# main.net
KiCad netlist of a schematic drawn in EAGLE
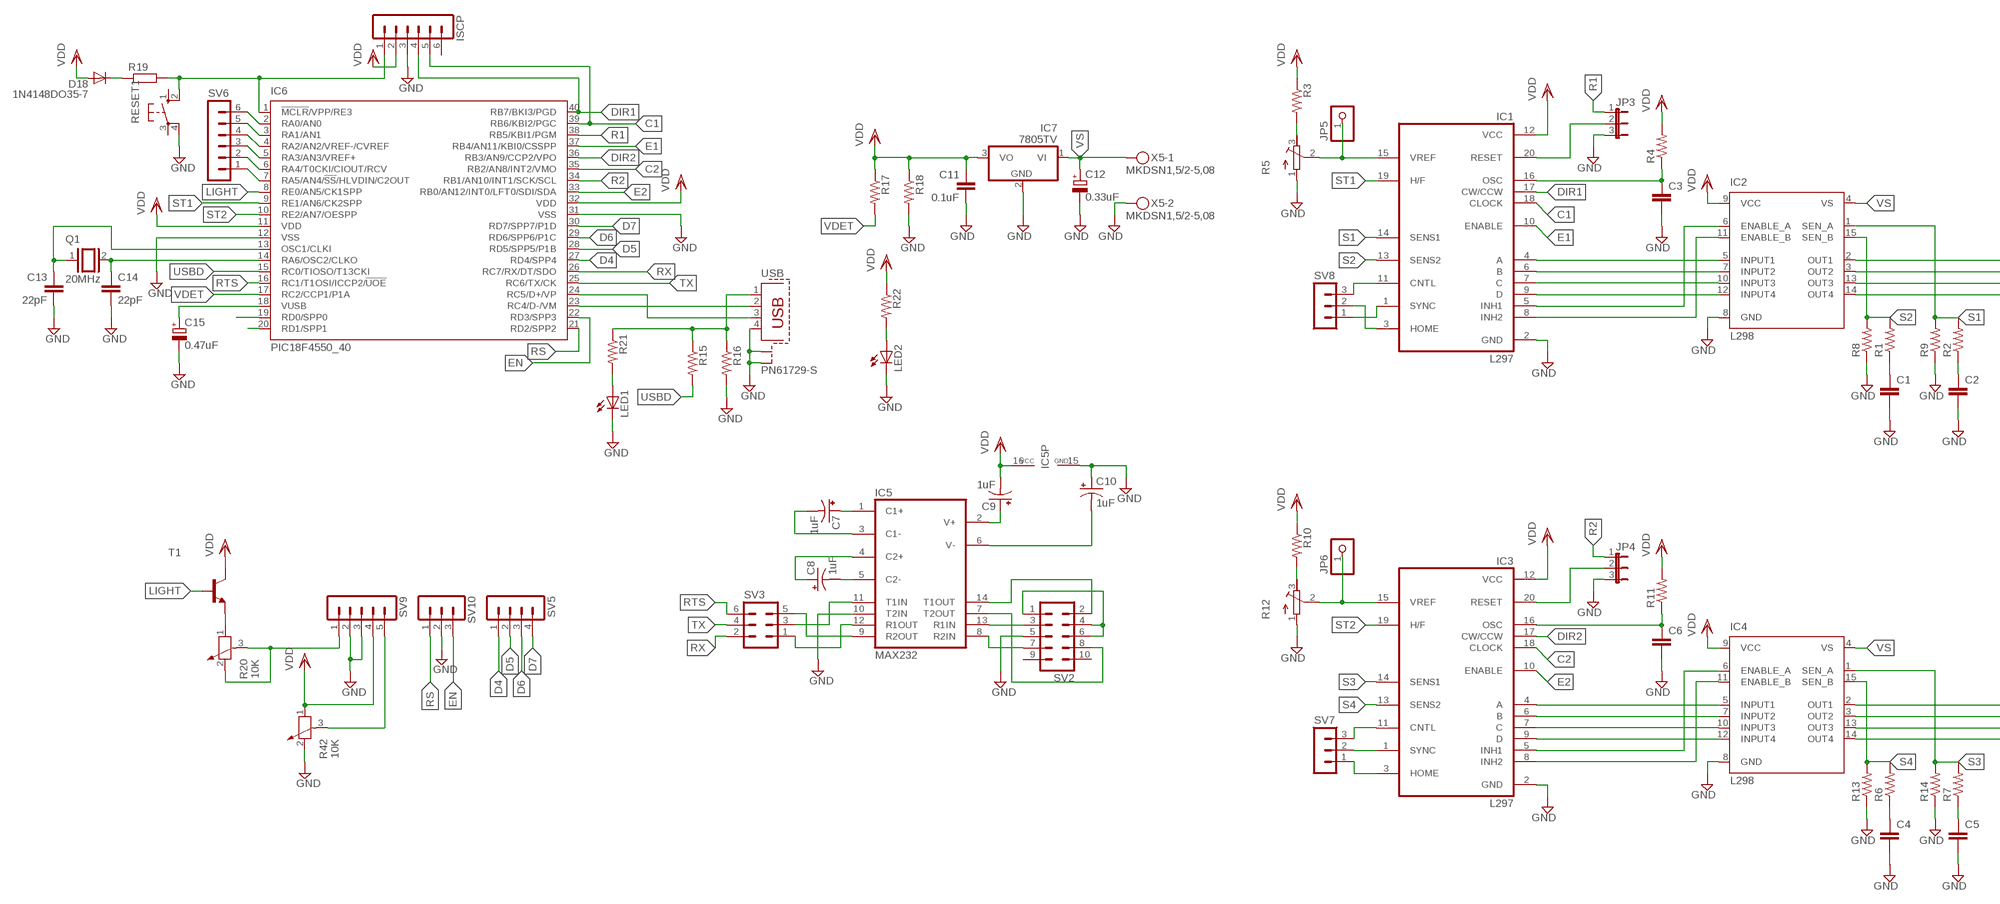
[diagram p0: schematic, sheet 1, part 1 of 2]
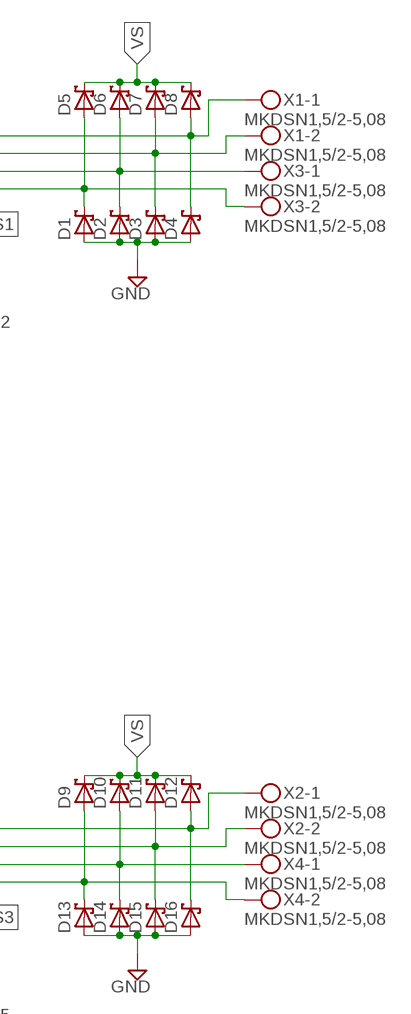
[diagram p1: schematic, sheet 1, part 2 of 2]

(export (version "E")
  (design (tool "Eeschema 10.0.6"))
  (components
    (comp (ref "C1")
      (value "C2.5/2")
      (footprint "eagle-import:C2.5-2")
      (libsource (lib "eagle-import") (part "C2.5/2"))
    )
    (comp (ref "C2")
      (value "C2.5/2")
      (footprint "eagle-import:C2.5-2")
      (libsource (lib "eagle-import") (part "C2.5/2"))
    )
    (comp (ref "C3")
      (value "C2.5/2")
      (footprint "eagle-import:C2.5-2")
      (libsource (lib "eagle-import") (part "C2.5/2"))
    )
    (comp (ref "C4")
      (value "C2.5/2")
      (footprint "eagle-import:C2.5-2")
      (libsource (lib "eagle-import") (part "C2.5/2"))
    )
    (comp (ref "C5")
      (value "C2.5/2")
      (footprint "eagle-import:C2.5-2")
      (libsource (lib "eagle-import") (part "C2.5/2"))
    )
    (comp (ref "C6")
      (value "C2.5/2")
      (footprint "eagle-import:C2.5-2")
      (libsource (lib "eagle-import") (part "C2.5/2"))
    )
    (comp (ref "C7")
      (value "1uF")
      (footprint "eagle-import:E2,5-6")
      (libsource (lib "eagle-import") (part "CPOL-USE2.5-6"))
    )
    (comp (ref "C8")
      (value "1uF")
      (footprint "eagle-import:E2,5-6")
      (libsource (lib "eagle-import") (part "CPOL-USE2.5-6"))
    )
    (comp (ref "C9")
      (value "1uF")
      (footprint "eagle-import:E2,5-6")
      (libsource (lib "eagle-import") (part "CPOL-USE2.5-6"))
    )
    (comp (ref "C10")
      (value "1uF")
      (footprint "eagle-import:E2,5-6")
      (libsource (lib "eagle-import") (part "CPOL-USE2.5-6"))
    )
    (comp (ref "C11")
      (value "0.1uF")
      (footprint "eagle-import:C025-025X050")
      (libsource (lib "eagle-import") (part "C-EU025-025X050"))
    )
    (comp (ref "C12")
      (value "0.33uF")
      (footprint "eagle-import:E2,5-6")
      (libsource (lib "eagle-import") (part "CPOL-EUE2.5-6"))
    )
    (comp (ref "C13")
      (value "22pF")
      (footprint "eagle-import:C025-024X044")
      (libsource (lib "eagle-import") (part "C-EU025-024X044"))
    )
    (comp (ref "C14")
      (value "22pF")
      (footprint "eagle-import:C025-024X044")
      (libsource (lib "eagle-import") (part "C-EU025-024X044"))
    )
    (comp (ref "C15")
      (value "0.47uF")
      (footprint "eagle-import:E2,5-6")
      (libsource (lib "eagle-import") (part "CPOL-EUE2.5-6"))
    )
    (comp (ref "D1")
      (value "SCHOTTKY-DIODEDO201T15")
      (footprint "eagle-import:DO201T15")
      (libsource (lib "eagle-import") (part "SCHOTTKY-DIODEDO201T15"))
    )
    (comp (ref "D2")
      (value "SCHOTTKY-DIODEDO201T15")
      (footprint "eagle-import:DO201T15")
      (libsource (lib "eagle-import") (part "SCHOTTKY-DIODEDO201T15"))
    )
    (comp (ref "D3")
      (value "SCHOTTKY-DIODEDO201T15")
      (footprint "eagle-import:DO201T15")
      (libsource (lib "eagle-import") (part "SCHOTTKY-DIODEDO201T15"))
    )
    (comp (ref "D4")
      (value "SCHOTTKY-DIODEDO201T15")
      (footprint "eagle-import:DO201T15")
      (libsource (lib "eagle-import") (part "SCHOTTKY-DIODEDO201T15"))
    )
    (comp (ref "D5")
      (value "SCHOTTKY-DIODEDO201T15")
      (footprint "eagle-import:DO201T15")
      (libsource (lib "eagle-import") (part "SCHOTTKY-DIODEDO201T15"))
    )
    (comp (ref "D6")
      (value "SCHOTTKY-DIODEDO201T15")
      (footprint "eagle-import:DO201T15")
      (libsource (lib "eagle-import") (part "SCHOTTKY-DIODEDO201T15"))
    )
    (comp (ref "D7")
      (value "SCHOTTKY-DIODEDO201T15")
      (footprint "eagle-import:DO201T15")
      (libsource (lib "eagle-import") (part "SCHOTTKY-DIODEDO201T15"))
    )
    (comp (ref "D8")
      (value "SCHOTTKY-DIODEDO201T15")
      (footprint "eagle-import:DO201T15")
      (libsource (lib "eagle-import") (part "SCHOTTKY-DIODEDO201T15"))
    )
    (comp (ref "D9")
      (value "SCHOTTKY-DIODEDO201T15")
      (footprint "eagle-import:DO201T15")
      (libsource (lib "eagle-import") (part "SCHOTTKY-DIODEDO201T15"))
    )
    (comp (ref "D10")
      (value "SCHOTTKY-DIODEDO201T15")
      (footprint "eagle-import:DO201T15")
      (libsource (lib "eagle-import") (part "SCHOTTKY-DIODEDO201T15"))
    )
    (comp (ref "D11")
      (value "SCHOTTKY-DIODEDO201T15")
      (footprint "eagle-import:DO201T15")
      (libsource (lib "eagle-import") (part "SCHOTTKY-DIODEDO201T15"))
    )
    (comp (ref "D12")
      (value "SCHOTTKY-DIODEDO201T15")
      (footprint "eagle-import:DO201T15")
      (libsource (lib "eagle-import") (part "SCHOTTKY-DIODEDO201T15"))
    )
    (comp (ref "D13")
      (value "SCHOTTKY-DIODEDO201T15")
      (footprint "eagle-import:DO201T15")
      (libsource (lib "eagle-import") (part "SCHOTTKY-DIODEDO201T15"))
    )
    (comp (ref "D14")
      (value "SCHOTTKY-DIODEDO201T15")
      (footprint "eagle-import:DO201T15")
      (libsource (lib "eagle-import") (part "SCHOTTKY-DIODEDO201T15"))
    )
    (comp (ref "D15")
      (value "SCHOTTKY-DIODEDO201T15")
      (footprint "eagle-import:DO201T15")
      (libsource (lib "eagle-import") (part "SCHOTTKY-DIODEDO201T15"))
    )
    (comp (ref "D16")
      (value "SCHOTTKY-DIODEDO201T15")
      (footprint "eagle-import:DO201T15")
      (libsource (lib "eagle-import") (part "SCHOTTKY-DIODEDO201T15"))
    )
    (comp (ref "D18")
      (value "1N4148DO35-7")
      (footprint "eagle-import:DO35-7")
      (libsource (lib "eagle-import") (part "1N4148DO35-7"))
    )
    (comp (ref "IC1")
      (value "L297")
      (footprint "eagle-import:DIL20")
      (fields (field (name "MPN") "L297/1"))
      (libsource (lib "eagle-import") (part "L297"))
    )
    (comp (ref "IC2")
      (value "L298")
      (footprint "eagle-import:MULTIWATT-15")
      (fields (field (name "MPN") "L298N"))
      (libsource (lib "eagle-import") (part "L298"))
    )
    (comp (ref "IC3")
      (value "L297")
      (footprint "eagle-import:DIL20")
      (fields (field (name "MPN") "L297/1"))
      (libsource (lib "eagle-import") (part "L297"))
    )
    (comp (ref "IC4")
      (value "L298")
      (footprint "eagle-import:MULTIWATT-15")
      (fields (field (name "MPN") "L298N"))
      (libsource (lib "eagle-import") (part "L298"))
    )
    (comp (ref "IC5")
      (value "MAX232")
      (footprint "eagle-import:DIL16")
      (fields (field (name "MF") "MAXIM") (field (name "MPN") "MAX232ACPE+"))
      (libsource (lib "eagle-import") (part "MAX232"))
    )
    (comp (ref "IC6")
      (value "PIC18F4550_40")
      (footprint "eagle-import:DIL40")
      (fields (field (name "MF") "MICROCHIP") (field (name "MPN") "PIC18F4550-I/P"))
      (libsource (lib "eagle-import") (part "PIC18F4_40550"))
    )
    (comp (ref "IC7")
      (value "7805TV")
      (footprint "eagle-import:TO220V")
      (libsource (lib "eagle-import") (part "78TV05"))
    )
    (comp (ref "ISCP")
      (value "MA06-1")
      (footprint "eagle-import:MA06-1")
      (libsource (lib "eagle-import") (part "MA06-1"))
    )
    (comp (ref "JP3")
      (value "JP2E")
      (footprint "eagle-import:JP2")
      (libsource (lib "eagle-import") (part "JP2E"))
    )
    (comp (ref "JP4")
      (value "JP2E")
      (footprint "eagle-import:JP2")
      (libsource (lib "eagle-import") (part "JP2E"))
    )
    (comp (ref "JP5")
      (value "PINHD-1X1")
      (footprint "eagle-import:1X01")
      (libsource (lib "eagle-import") (part "PINHD-1X1"))
    )
    (comp (ref "JP6")
      (value "PINHD-1X1")
      (footprint "eagle-import:1X01")
      (libsource (lib "eagle-import") (part "PINHD-1X1"))
    )
    (comp (ref "LED1")
      (value "LED5MM")
      (footprint "eagle-import:LED5MM")
      (libsource (lib "eagle-import") (part "LED5MM"))
    )
    (comp (ref "LED2")
      (value "LED5MM")
      (footprint "eagle-import:LED5MM")
      (libsource (lib "eagle-import") (part "LED5MM"))
    )
    (comp (ref "Q1")
      (value "20MHz")
      (footprint "eagle-import:QS")
      (libsource (lib "eagle-import") (part "XTAL/S"))
    )
    (comp (ref "R1")
      (value "R-US_0204/7")
      (footprint "eagle-import:0204_7")
      (libsource (lib "eagle-import") (part "R-US_0204/7"))
    )
    (comp (ref "R2")
      (value "R-US_0204/7")
      (footprint "eagle-import:0204_7")
      (libsource (lib "eagle-import") (part "R-US_0204/7"))
    )
    (comp (ref "R3")
      (value "R-US_0204/7")
      (footprint "eagle-import:0204_7")
      (libsource (lib "eagle-import") (part "R-US_0204/7"))
    )
    (comp (ref "R4")
      (value "R-US_0204/7")
      (footprint "eagle-import:0204_7")
      (libsource (lib "eagle-import") (part "R-US_0204/7"))
    )
    (comp (ref "R5")
      (value "R-TRIMM64Y")
      (footprint "eagle-import:RTRIM64Y")
      (libsource (lib "eagle-import") (part "R-TRIMM64Y"))
    )
    (comp (ref "R6")
      (value "R-US_0204/7")
      (footprint "eagle-import:0204_7")
      (libsource (lib "eagle-import") (part "R-US_0204/7"))
    )
    (comp (ref "R7")
      (value "R-US_0204/7")
      (footprint "eagle-import:0204_7")
      (libsource (lib "eagle-import") (part "R-US_0204/7"))
    )
    (comp (ref "R8")
      (value "R-US_0411/15")
      (footprint "eagle-import:0411_15")
      (libsource (lib "eagle-import") (part "R-US_0411/15"))
    )
    (comp (ref "R9")
      (value "R-US_0411/15")
      (footprint "eagle-import:0411_15")
      (libsource (lib "eagle-import") (part "R-US_0411/15"))
    )
    (comp (ref "R10")
      (value "R-US_0204/7")
      (footprint "eagle-import:0204_7")
      (libsource (lib "eagle-import") (part "R-US_0204/7"))
    )
    (comp (ref "R11")
      (value "R-US_0204/7")
      (footprint "eagle-import:0204_7")
      (libsource (lib "eagle-import") (part "R-US_0204/7"))
    )
    (comp (ref "R12")
      (value "R-TRIMM64Y")
      (footprint "eagle-import:RTRIM64Y")
      (libsource (lib "eagle-import") (part "R-TRIMM64Y"))
    )
    (comp (ref "R13")
      (value "R-US_0411/15")
      (footprint "eagle-import:0411_15")
      (libsource (lib "eagle-import") (part "R-US_0411/15"))
    )
    (comp (ref "R14")
      (value "R-US_0411/15")
      (footprint "eagle-import:0411_15")
      (libsource (lib "eagle-import") (part "R-US_0411/15"))
    )
    (comp (ref "R15")
      (value "R-US_0204/7")
      (footprint "eagle-import:0204_7")
      (libsource (lib "eagle-import") (part "R-US_0204/7"))
    )
    (comp (ref "R16")
      (value "R-US_0204/7")
      (footprint "eagle-import:0204_7")
      (libsource (lib "eagle-import") (part "R-US_0204/7"))
    )
    (comp (ref "R17")
      (value "R-US_0204/7")
      (footprint "eagle-import:0204_7")
      (libsource (lib "eagle-import") (part "R-US_0204/7"))
    )
    (comp (ref "R18")
      (value "R-US_0204/7")
      (footprint "eagle-import:0204_7")
      (libsource (lib "eagle-import") (part "R-US_0204/7"))
    )
    (comp (ref "R19")
      (value "R-EU_0204/7")
      (footprint "eagle-import:0204_7")
      (libsource (lib "eagle-import") (part "R-EU_0204/7"))
    )
    (comp (ref "R20")
      (value "10K")
      (footprint "eagle-import:PT-10")
      (libsource (lib "eagle-import") (part "POTENTIOMETER_PT-10"))
    )
    (comp (ref "R21")
      (value "R-US_0204/7")
      (footprint "eagle-import:0204_7")
      (libsource (lib "eagle-import") (part "R-US_0204/7"))
    )
    (comp (ref "R22")
      (value "R-US_0204/7")
      (footprint "eagle-import:0204_7")
      (libsource (lib "eagle-import") (part "R-US_0204/7"))
    )
    (comp (ref "R42")
      (value "10K")
      (footprint "eagle-import:PT-10")
      (libsource (lib "eagle-import") (part "POTENTIOMETER_PT-10"))
    )
    (comp (ref "RESET1")
      (value "10-XX")
      (footprint "eagle-import:B3F-10XX")
      (fields (field (name "MPN") "B3F-1000"))
      (libsource (lib "eagle-import") (part "10-XX"))
    )
    (comp (ref "SV2")
      (value "MA05-2")
      (footprint "eagle-import:MA05-2")
      (libsource (lib "eagle-import") (part "MA05-2"))
    )
    (comp (ref "SV3")
      (value "MA03-2")
      (footprint "eagle-import:MA03-2")
      (libsource (lib "eagle-import") (part "MA03-2"))
    )
    (comp (ref "SV5")
      (value "MA04-1")
      (footprint "eagle-import:MA04-1")
      (libsource (lib "eagle-import") (part "MA04-1"))
    )
    (comp (ref "SV6")
      (value "MA06-1")
      (footprint "eagle-import:MA06-1")
      (libsource (lib "eagle-import") (part "MA06-1"))
    )
    (comp (ref "SV7")
      (value "MA03-1")
      (footprint "eagle-import:MA03-1")
      (libsource (lib "eagle-import") (part "MA03-1"))
    )
    (comp (ref "SV8")
      (value "MA03-1")
      (footprint "eagle-import:MA03-1")
      (libsource (lib "eagle-import") (part "MA03-1"))
    )
    (comp (ref "SV9")
      (value "MA05-1")
      (footprint "eagle-import:MA05-1")
      (libsource (lib "eagle-import") (part "MA05-1"))
    )
    (comp (ref "SV10")
      (value "MA03-1")
      (footprint "eagle-import:MA03-1")
      (libsource (lib "eagle-import") (part "MA03-1"))
    )
    (comp (ref "T1")
      (value "BC548-NPN-TO92-CBE")
      (footprint "eagle-import:TO92-CBE")
      (libsource (lib "eagle-import") (part "-NPN-TO92-CBEBC548"))
    )
    (comp (ref "USB")
      (value "PN61729-S")
      (footprint "eagle-import:PN61729-S")
      (libsource (lib "eagle-import") (part "PN61729-S"))
    )
    (comp (ref "X1")
      (value "MKDSN1,5/2-5,08")
      (footprint "eagle-import:MKDSN1,5_2-5,08")
      (fields (field (name "MPN") "MKDSN 1,5/2-5.08"))
      (libsource (lib "eagle-import") (part "MKDSN1,5/2-5,08"))
    )
    (comp (ref "X2")
      (value "MKDSN1,5/2-5,08")
      (footprint "eagle-import:MKDSN1,5_2-5,08")
      (fields (field (name "MPN") "MKDSN 1,5/2-5.08"))
      (libsource (lib "eagle-import") (part "MKDSN1,5/2-5,08"))
    )
    (comp (ref "X3")
      (value "MKDSN1,5/2-5,08")
      (footprint "eagle-import:MKDSN1,5_2-5,08")
      (fields (field (name "MPN") "MKDSN 1,5/2-5.08"))
      (libsource (lib "eagle-import") (part "MKDSN1,5/2-5,08"))
    )
    (comp (ref "X4")
      (value "MKDSN1,5/2-5,08")
      (footprint "eagle-import:MKDSN1,5_2-5,08")
      (fields (field (name "MPN") "MKDSN 1,5/2-5.08"))
      (libsource (lib "eagle-import") (part "MKDSN1,5/2-5,08"))
    )
    (comp (ref "X5")
      (value "MKDSN1,5/2-5,08")
      (footprint "eagle-import:MKDSN1,5_2-5,08")
      (fields (field (name "MPN") "MKDSN 1,5/2-5.08"))
      (libsource (lib "eagle-import") (part "MKDSN1,5/2-5,08"))
    )
  )
  (nets
    (net (code "1") (name "C1") (class "Default")
      (node (ref "IC1") (pin "18") (pinfunction "CLOCK_18") (pintype "input"))
      (node (ref "IC6") (pin "39") (pinfunction "RB6/KBI2/PGC_39") (pintype "bidirectional"))
      (node (ref "ISCP") (pin "5") (pinfunction "5_5") (pintype "passive"))
    )
    (net (code "2") (name "C2") (class "Default")
      (node (ref "IC3") (pin "18") (pinfunction "CLOCK_18") (pintype "input"))
      (node (ref "IC6") (pin "35") (pinfunction "RB2/AN8/INT2/VMO_35") (pintype "bidirectional"))
    )
    (net (code "3") (name "D4") (class "Default")
      (node (ref "IC6") (pin "27") (pinfunction "RD4/SPP4_27") (pintype "bidirectional"))
      (node (ref "SV5") (pin "1") (pinfunction "1_1") (pintype "passive"))
    )
    (net (code "4") (name "D5") (class "Default")
      (node (ref "IC6") (pin "28") (pinfunction "RD5/SPP5/P1B_28") (pintype "bidirectional"))
      (node (ref "SV5") (pin "2") (pinfunction "2_2") (pintype "passive"))
    )
    (net (code "5") (name "D6") (class "Default")
      (node (ref "IC6") (pin "29") (pinfunction "RD6/SPP6/P1C_29") (pintype "bidirectional"))
      (node (ref "SV5") (pin "3") (pinfunction "3_3") (pintype "passive"))
    )
    (net (code "6") (name "D7") (class "Default")
      (node (ref "IC6") (pin "30") (pinfunction "RD7/SPP7/P1D_30") (pintype "bidirectional"))
      (node (ref "SV5") (pin "4") (pinfunction "4_4") (pintype "passive"))
    )
    (net (code "7") (name "DIR1") (class "Default")
      (node (ref "IC1") (pin "17") (pinfunction "CW/CCW_17") (pintype "input"))
      (node (ref "IC6") (pin "40") (pinfunction "RB7/BKI3/PGD_40") (pintype "bidirectional"))
      (node (ref "ISCP") (pin "4") (pinfunction "4_4") (pintype "passive"))
    )
    (net (code "8") (name "DIR2") (class "Default")
      (node (ref "IC3") (pin "17") (pinfunction "CW/CCW_17") (pintype "input"))
      (node (ref "IC6") (pin "36") (pinfunction "RB3/AN9/CCP2/VPO_36") (pintype "bidirectional"))
    )
    (net (code "9") (name "E1") (class "Default")
      (node (ref "IC1") (pin "10") (pinfunction "ENABLE_10") (pintype "input"))
      (node (ref "IC6") (pin "37") (pinfunction "RB4/AN11/KBI0/CSSPP_37") (pintype "bidirectional"))
    )
    (net (code "10") (name "E2") (class "Default")
      (node (ref "IC3") (pin "10") (pinfunction "ENABLE_10") (pintype "input"))
      (node (ref "IC6") (pin "33") (pinfunction "RB0/AN12/INT0/LFT0/SDI/SDA_33") (pintype "bidirectional"))
    )
    (net (code "11") (name "EN") (class "Default")
      (node (ref "IC6") (pin "22") (pinfunction "RD3/SPP3_22") (pintype "bidirectional"))
      (node (ref "SV10") (pin "3") (pinfunction "3_3") (pintype "passive"))
    )
    (net (code "12") (name "GND") (class "Default")
      (node (ref "C1") (pin "2") (pinfunction "2_2") (pintype "passive"))
      (node (ref "C10") (pin "+") (pinfunction "+_+") (pintype "passive"))
      (node (ref "C11") (pin "2") (pinfunction "2_2") (pintype "passive"))
      (node (ref "C12") (pin "-") (pinfunction "-_-") (pintype "passive"))
      (node (ref "C13") (pin "2") (pinfunction "2_2") (pintype "passive"))
      (node (ref "C14") (pin "2") (pinfunction "2_2") (pintype "passive"))
      (node (ref "C15") (pin "-") (pinfunction "-_-") (pintype "passive"))
      (node (ref "C2") (pin "2") (pinfunction "2_2") (pintype "passive"))
      (node (ref "C3") (pin "2") (pinfunction "2_2") (pintype "passive"))
      (node (ref "C4") (pin "2") (pinfunction "2_2") (pintype "passive"))
      (node (ref "C5") (pin "2") (pinfunction "2_2") (pintype "passive"))
      (node (ref "C6") (pin "2") (pinfunction "2_2") (pintype "passive"))
      (node (ref "D1") (pin "A") (pinfunction "A_A") (pintype "passive"))
      (node (ref "D13") (pin "A") (pinfunction "A_A") (pintype "passive"))
      (node (ref "D14") (pin "A") (pinfunction "A_A") (pintype "passive"))
      (node (ref "D15") (pin "A") (pinfunction "A_A") (pintype "passive"))
      (node (ref "D16") (pin "A") (pinfunction "A_A") (pintype "passive"))
      (node (ref "D2") (pin "A") (pinfunction "A_A") (pintype "passive"))
      (node (ref "D3") (pin "A") (pinfunction "A_A") (pintype "passive"))
      (node (ref "D4") (pin "A") (pinfunction "A_A") (pintype "passive"))
      (node (ref "IC1") (pin "2") (pinfunction "GND_2") (pintype "power_in"))
      (node (ref "IC2") (pin "8") (pinfunction "GND_8") (pintype "power_in"))
      (node (ref "IC3") (pin "2") (pinfunction "GND_2") (pintype "power_in"))
      (node (ref "IC4") (pin "8") (pinfunction "GND_8") (pintype "power_in"))
      (node (ref "IC5") (pin "10") (pinfunction "T2IN_10") (pintype "input"))
      (node (ref "IC5") (pin "15") (pinfunction "GND_15") (pintype "power_in"))
      (node (ref "IC6") (pin "12") (pinfunction "VSS_12") (pintype "power_in"))
      (node (ref "IC6") (pin "31") (pinfunction "VSS_31") (pintype "power_in"))
      (node (ref "IC7") (pin "2") (pinfunction "GND_2") (pintype "passive"))
      (node (ref "ISCP") (pin "3") (pinfunction "3_3") (pintype "passive"))
      (node (ref "JP3") (pin "3") (pinfunction "3_3") (pintype "passive"))
      (node (ref "JP4") (pin "3") (pinfunction "3_3") (pintype "passive"))
      (node (ref "LED1") (pin "K") (pinfunction "C_K") (pintype "passive"))
      (node (ref "LED2") (pin "K") (pinfunction "C_K") (pintype "passive"))
      (node (ref "R12") (pin "1") (pinfunction "E_1") (pintype "passive"))
      (node (ref "R13") (pin "1") (pinfunction "1_1") (pintype "passive"))
      (node (ref "R14") (pin "1") (pinfunction "1_1") (pintype "passive"))
      (node (ref "R16") (pin "2") (pinfunction "2_2") (pintype "passive"))
      (node (ref "R18") (pin "2") (pinfunction "2_2") (pintype "passive"))
      (node (ref "R42") (pin "2") (pinfunction "2_2") (pintype "passive"))
      (node (ref "R5") (pin "1") (pinfunction "E_1") (pintype "passive"))
      (node (ref "R8") (pin "1") (pinfunction "1_1") (pintype "passive"))
      (node (ref "R9") (pin "1") (pinfunction "1_1") (pintype "passive"))
      (node (ref "RESET1") (pin "4") (pinfunction "P1_4") (pintype "passive"))
      (node (ref "SV10") (pin "2") (pinfunction "2_2") (pintype "passive"))
      (node (ref "SV2") (pin "5") (pinfunction "5_5") (pintype "passive"))
      (node (ref "SV9") (pin "2") (pinfunction "2_2") (pintype "passive"))
      (node (ref "SV9") (pin "3") (pinfunction "3_3") (pintype "passive"))
      (node (ref "USB") (pin "4") (pinfunction "4_4") (pintype "passive"))
      (node (ref "USB") (pin "S1") (pinfunction "S1_S1") (pintype "passive"))
      (node (ref "USB") (pin "S2") (pinfunction "S2_S2") (pintype "passive"))
      (node (ref "X5") (pin "2") (pinfunction "KL_2") (pintype "passive"))
    )
    (net (code "13") (name "LIGHT") (class "Default")
      (node (ref "IC6") (pin "8") (pinfunction "RE0/AN5/CK1SPP_8") (pintype "bidirectional"))
      (node (ref "T1") (pin "B") (pinfunction "B_B") (pintype "passive"))
    )
    (net (code "14") (name "Net-(C1-Pad1)") (class "Default")
      (node (ref "C1") (pin "1") (pinfunction "1_1") (pintype "passive"))
      (node (ref "R1") (pin "1") (pinfunction "1_1") (pintype "passive"))
    )
    (net (code "15") (name "Net-(C2-Pad1)") (class "Default")
      (node (ref "C2") (pin "1") (pinfunction "1_1") (pintype "passive"))
      (node (ref "R2") (pin "1") (pinfunction "1_1") (pintype "passive"))
    )
    (net (code "16") (name "Net-(C4-Pad1)") (class "Default")
      (node (ref "C4") (pin "1") (pinfunction "1_1") (pintype "passive"))
      (node (ref "R6") (pin "1") (pinfunction "1_1") (pintype "passive"))
    )
    (net (code "17") (name "Net-(C5-Pad1)") (class "Default")
      (node (ref "C5") (pin "1") (pinfunction "1_1") (pintype "passive"))
      (node (ref "R7") (pin "1") (pinfunction "1_1") (pintype "passive"))
    )
    (net (code "18") (name "Net-(D18-PadC)") (class "Default")
      (node (ref "D18") (pin "C") (pinfunction "C_C") (pintype "passive"))
      (node (ref "R19") (pin "1") (pinfunction "1_1") (pintype "passive"))
    )
    (net (code "19") (name "Net-(IC1-A)") (class "Default")
      (node (ref "IC1") (pin "4") (pinfunction "A_4") (pintype "output"))
      (node (ref "IC2") (pin "5") (pinfunction "INPUT1_5") (pintype "input"))
    )
    (net (code "20") (name "Net-(IC1-B)") (class "Default")
      (node (ref "IC1") (pin "6") (pinfunction "B_6") (pintype "output"))
      (node (ref "IC2") (pin "7") (pinfunction "INPUT2_7") (pintype "input"))
    )
    (net (code "21") (name "Net-(IC1-C)") (class "Default")
      (node (ref "IC1") (pin "7") (pinfunction "C_7") (pintype "output"))
      (node (ref "IC2") (pin "10") (pinfunction "INPUT3_10") (pintype "input"))
    )
    (net (code "22") (name "Net-(IC1-CNTL)") (class "Default")
      (node (ref "IC1") (pin "11") (pinfunction "CNTL_11") (pintype "input"))
      (node (ref "SV8") (pin "3") (pinfunction "3_3") (pintype "passive"))
    )
    (net (code "23") (name "Net-(IC1-D)") (class "Default")
      (node (ref "IC1") (pin "9") (pinfunction "D_9") (pintype "output"))
      (node (ref "IC2") (pin "12") (pinfunction "INPUT4_12") (pintype "input"))
    )
    (net (code "24") (name "Net-(IC1-HOME)") (class "Default")
      (node (ref "IC1") (pin "3") (pinfunction "HOME_3") (pintype "output"))
      (node (ref "SV8") (pin "2") (pinfunction "2_2") (pintype "passive"))
    )
    (net (code "25") (name "Net-(IC1-INH1)") (class "Default")
      (node (ref "IC1") (pin "5") (pinfunction "INH1_5") (pintype "output"))
      (node (ref "IC2") (pin "6") (pinfunction "ENABLE_A_6") (pintype "input"))
    )
    (net (code "26") (name "Net-(IC1-INH2)") (class "Default")
      (node (ref "IC1") (pin "8") (pinfunction "INH2_8") (pintype "output"))
      (node (ref "IC2") (pin "11") (pinfunction "ENABLE_B_11") (pintype "input"))
    )
    (net (code "27") (name "Net-(IC1-OSC)") (class "Default")
      (node (ref "C3") (pin "1") (pinfunction "1_1") (pintype "passive"))
      (node (ref "IC1") (pin "16") (pinfunction "OSC_16") (pintype "bidirectional"))
      (node (ref "R4") (pin "1") (pinfunction "1_1") (pintype "passive"))
    )
    (net (code "28") (name "Net-(IC1-RESET)") (class "Default")
      (node (ref "IC1") (pin "20") (pinfunction "RESET_20") (pintype "input"))
      (node (ref "JP3") (pin "2") (pinfunction "2_2") (pintype "passive"))
    )
    (net (code "29") (name "Net-(IC1-SYNC)") (class "Default")
      (node (ref "IC1") (pin "1") (pinfunction "SYNC_1") (pintype "output"))
      (node (ref "SV8") (pin "1") (pinfunction "1_1") (pintype "passive"))
    )
    (net (code "30") (name "Net-(IC1-VREF)") (class "Default")
      (node (ref "IC1") (pin "15") (pinfunction "VREF_15") (pintype "input"))
      (node (ref "JP5") (pin "1") (pinfunction "1_1") (pintype "passive"))
      (node (ref "R5") (pin "2") (pinfunction "S_2") (pintype "passive"))
    )
    (net (code "31") (name "Net-(IC2-OUT1)") (class "Default")
      (node (ref "D4") (pin "C") (pinfunction "C_C") (pintype "passive"))
      (node (ref "D8") (pin "A") (pinfunction "A_A") (pintype "passive"))
      (node (ref "IC2") (pin "2") (pinfunction "OUT1_2") (pintype "output"))
      (node (ref "X1") (pin "1") (pinfunction "KL_1") (pintype "passive"))
    )
    (net (code "32") (name "Net-(IC2-OUT2)") (class "Default")
      (node (ref "D3") (pin "C") (pinfunction "C_C") (pintype "passive"))
      (node (ref "D7") (pin "A") (pinfunction "A_A") (pintype "passive"))
      (node (ref "IC2") (pin "3") (pinfunction "OUT2_3") (pintype "output"))
      (node (ref "X1") (pin "2") (pinfunction "KL_2") (pintype "passive"))
    )
    (net (code "33") (name "Net-(IC2-OUT3)") (class "Default")
      (node (ref "D2") (pin "C") (pinfunction "C_C") (pintype "passive"))
      (node (ref "D6") (pin "A") (pinfunction "A_A") (pintype "passive"))
      (node (ref "IC2") (pin "13") (pinfunction "OUT3_13") (pintype "output"))
      (node (ref "X3") (pin "1") (pinfunction "KL_1") (pintype "passive"))
    )
    (net (code "34") (name "Net-(IC2-OUT4)") (class "Default")
      (node (ref "D1") (pin "C") (pinfunction "C_C") (pintype "passive"))
      (node (ref "D5") (pin "A") (pinfunction "A_A") (pintype "passive"))
      (node (ref "IC2") (pin "14") (pinfunction "OUT4_14") (pintype "output"))
      (node (ref "X3") (pin "2") (pinfunction "KL_2") (pintype "passive"))
    )
    (net (code "35") (name "Net-(IC3-A)") (class "Default")
      (node (ref "IC3") (pin "4") (pinfunction "A_4") (pintype "output"))
      (node (ref "IC4") (pin "5") (pinfunction "INPUT1_5") (pintype "input"))
    )
    (net (code "36") (name "Net-(IC3-B)") (class "Default")
      (node (ref "IC3") (pin "6") (pinfunction "B_6") (pintype "output"))
      (node (ref "IC4") (pin "7") (pinfunction "INPUT2_7") (pintype "input"))
    )
    (net (code "37") (name "Net-(IC3-C)") (class "Default")
      (node (ref "IC3") (pin "7") (pinfunction "C_7") (pintype "output"))
      (node (ref "IC4") (pin "10") (pinfunction "INPUT3_10") (pintype "input"))
    )
    (net (code "38") (name "Net-(IC3-CNTL)") (class "Default")
      (node (ref "IC3") (pin "11") (pinfunction "CNTL_11") (pintype "input"))
      (node (ref "SV7") (pin "3") (pinfunction "3_3") (pintype "passive"))
    )
    (net (code "39") (name "Net-(IC3-D)") (class "Default")
      (node (ref "IC3") (pin "9") (pinfunction "D_9") (pintype "output"))
      (node (ref "IC4") (pin "12") (pinfunction "INPUT4_12") (pintype "input"))
    )
    (net (code "40") (name "Net-(IC3-HOME)") (class "Default")
      (node (ref "IC3") (pin "3") (pinfunction "HOME_3") (pintype "output"))
      (node (ref "SV7") (pin "1") (pinfunction "1_1") (pintype "passive"))
    )
    (net (code "41") (name "Net-(IC3-INH1)") (class "Default")
      (node (ref "IC3") (pin "5") (pinfunction "INH1_5") (pintype "output"))
      (node (ref "IC4") (pin "6") (pinfunction "ENABLE_A_6") (pintype "input"))
    )
    (net (code "42") (name "Net-(IC3-INH2)") (class "Default")
      (node (ref "IC3") (pin "8") (pinfunction "INH2_8") (pintype "output"))
      (node (ref "IC4") (pin "11") (pinfunction "ENABLE_B_11") (pintype "input"))
    )
    (net (code "43") (name "Net-(IC3-OSC)") (class "Default")
      (node (ref "C6") (pin "1") (pinfunction "1_1") (pintype "passive"))
      (node (ref "IC3") (pin "16") (pinfunction "OSC_16") (pintype "bidirectional"))
      (node (ref "R11") (pin "1") (pinfunction "1_1") (pintype "passive"))
    )
    (net (code "44") (name "Net-(IC3-RESET)") (class "Default")
      (node (ref "IC3") (pin "20") (pinfunction "RESET_20") (pintype "input"))
      (node (ref "JP4") (pin "2") (pinfunction "2_2") (pintype "passive"))
    )
    (net (code "45") (name "Net-(IC3-SYNC)") (class "Default")
      (node (ref "IC3") (pin "1") (pinfunction "SYNC_1") (pintype "output"))
      (node (ref "SV7") (pin "2") (pinfunction "2_2") (pintype "passive"))
    )
    (net (code "46") (name "Net-(IC3-VREF)") (class "Default")
      (node (ref "IC3") (pin "15") (pinfunction "VREF_15") (pintype "input"))
      (node (ref "JP6") (pin "1") (pinfunction "1_1") (pintype "passive"))
      (node (ref "R12") (pin "2") (pinfunction "S_2") (pintype "passive"))
    )
    (net (code "47") (name "Net-(IC4-OUT1)") (class "Default")
      (node (ref "D12") (pin "A") (pinfunction "A_A") (pintype "passive"))
      (node (ref "D16") (pin "C") (pinfunction "C_C") (pintype "passive"))
      (node (ref "IC4") (pin "2") (pinfunction "OUT1_2") (pintype "output"))
      (node (ref "X2") (pin "1") (pinfunction "KL_1") (pintype "passive"))
    )
    (net (code "48") (name "Net-(IC4-OUT2)") (class "Default")
      (node (ref "D11") (pin "A") (pinfunction "A_A") (pintype "passive"))
      (node (ref "D15") (pin "C") (pinfunction "C_C") (pintype "passive"))
      (node (ref "IC4") (pin "3") (pinfunction "OUT2_3") (pintype "output"))
      (node (ref "X2") (pin "2") (pinfunction "KL_2") (pintype "passive"))
    )
    (net (code "49") (name "Net-(IC4-OUT3)") (class "Default")
      (node (ref "D10") (pin "A") (pinfunction "A_A") (pintype "passive"))
      (node (ref "D14") (pin "C") (pinfunction "C_C") (pintype "passive"))
      (node (ref "IC4") (pin "13") (pinfunction "OUT3_13") (pintype "output"))
      (node (ref "X4") (pin "1") (pinfunction "KL_1") (pintype "passive"))
    )
    (net (code "50") (name "Net-(IC4-OUT4)") (class "Default")
      (node (ref "D13") (pin "C") (pinfunction "C_C") (pintype "passive"))
      (node (ref "D9") (pin "A") (pinfunction "A_A") (pintype "passive"))
      (node (ref "IC4") (pin "14") (pinfunction "OUT4_14") (pintype "output"))
      (node (ref "X4") (pin "2") (pinfunction "KL_2") (pintype "passive"))
    )
    (net (code "51") (name "Net-(IC5A-C1+)") (class "Default")
      (node (ref "C7") (pin "+") (pinfunction "+_+") (pintype "passive"))
      (node (ref "IC5") (pin "1") (pinfunction "C1+_1") (pintype "bidirectional"))
    )
    (net (code "52") (name "Net-(IC5A-C1-)") (class "Default")
      (node (ref "C7") (pin "-") (pinfunction "-_-") (pintype "passive"))
      (node (ref "IC5") (pin "3") (pinfunction "C1-_3") (pintype "bidirectional"))
    )
    (net (code "53") (name "Net-(IC5A-C2+)") (class "Default")
      (node (ref "C8") (pin "+") (pinfunction "+_+") (pintype "passive"))
      (node (ref "IC5") (pin "4") (pinfunction "C2+_4") (pintype "bidirectional"))
    )
    (net (code "54") (name "Net-(IC5A-C2-)") (class "Default")
      (node (ref "C8") (pin "-") (pinfunction "-_-") (pintype "passive"))
      (node (ref "IC5") (pin "5") (pinfunction "C2-_5") (pintype "bidirectional"))
    )
    (net (code "55") (name "Net-(IC5A-R1IN)") (class "Default")
      (node (ref "IC5") (pin "13") (pinfunction "R1IN_13") (pintype "input"))
      (node (ref "SV2") (pin "3") (pinfunction "3_3") (pintype "passive"))
    )
    (net (code "56") (name "Net-(IC5A-R1OUT)") (class "Default")
      (node (ref "IC5") (pin "12") (pinfunction "R1OUT_12") (pintype "output"))
      (node (ref "SV3") (pin "1") (pinfunction "1_1") (pintype "passive"))
    )
    (net (code "57") (name "Net-(IC5A-R2IN)") (class "Default")
      (node (ref "IC5") (pin "8") (pinfunction "R2IN_8") (pintype "input"))
      (node (ref "SV2") (pin "7") (pinfunction "7_7") (pintype "passive"))
    )
    (net (code "58") (name "Net-(IC5A-R2OUT)") (class "Default")
      (node (ref "IC5") (pin "9") (pinfunction "R2OUT_9") (pintype "output"))
      (node (ref "SV3") (pin "5") (pinfunction "5_5") (pintype "passive"))
    )
    (net (code "59") (name "Net-(IC5A-T1IN)") (class "Default")
      (node (ref "IC5") (pin "11") (pinfunction "T1IN_11") (pintype "input"))
      (node (ref "SV3") (pin "3") (pinfunction "3_3") (pintype "passive"))
    )
    (net (code "60") (name "Net-(IC5A-T1OUT)") (class "Default")
      (node (ref "IC5") (pin "14") (pinfunction "T1OUT_14") (pintype "output"))
      (node (ref "SV2") (pin "2") (pinfunction "2_2") (pintype "passive"))
    )
    (net (code "61") (name "Net-(IC5A-T2OUT)") (class "Default")
      (node (ref "IC5") (pin "7") (pinfunction "T2OUT_7") (pintype "output"))
      (node (ref "SV2") (pin "8") (pinfunction "8_8") (pintype "passive"))
    )
    (net (code "62") (name "Net-(IC5A-V+)") (class "Default")
      (node (ref "C9") (pin "+") (pinfunction "+_+") (pintype "passive"))
      (node (ref "IC5") (pin "2") (pinfunction "V+_2") (pintype "bidirectional"))
    )
    (net (code "63") (name "Net-(IC5A-V-)") (class "Default")
      (node (ref "C10") (pin "-") (pinfunction "-_-") (pintype "passive"))
      (node (ref "IC5") (pin "6") (pinfunction "V-_6") (pintype "bidirectional"))
    )
    (net (code "64") (name "Net-(IC6-OSC1{slash}CLKI)") (class "Default")
      (node (ref "C13") (pin "1") (pinfunction "1_1") (pintype "passive"))
      (node (ref "IC6") (pin "13") (pinfunction "OSC1/CLKI_13") (pintype "input"))
      (node (ref "Q1") (pin "1") (pinfunction "1_1") (pintype "passive"))
    )
    (net (code "65") (name "Net-(IC6-RA0{slash}AN0)") (class "Default")
      (node (ref "IC6") (pin "2") (pinfunction "RA0/AN0_2") (pintype "bidirectional"))
      (node (ref "SV6") (pin "6") (pinfunction "6_6") (pintype "passive"))
    )
    (net (code "66") (name "Net-(IC6-RA1{slash}AN1)") (class "Default")
      (node (ref "IC6") (pin "3") (pinfunction "RA1/AN1_3") (pintype "bidirectional"))
      (node (ref "SV6") (pin "5") (pinfunction "5_5") (pintype "passive"))
    )
    (net (code "67") (name "Net-(IC6-RA2{slash}AN2{slash}VREF-{slash}CVREF)") (class "Default")
      (node (ref "IC6") (pin "4") (pinfunction "RA2/AN2/VREF-/CVREF_4") (pintype "bidirectional"))
      (node (ref "SV6") (pin "4") (pinfunction "4_4") (pintype "passive"))
    )
    (net (code "68") (name "Net-(IC6-RA3{slash}AN3{slash}VREF+)") (class "Default")
      (node (ref "IC6") (pin "5") (pinfunction "RA3/AN3/VREF+_5") (pintype "bidirectional"))
      (node (ref "SV6") (pin "3") (pinfunction "3_3") (pintype "passive"))
    )
    (net (code "69") (name "Net-(IC6-RA4{slash}T0CKI{slash}CIOUT{slash}RCV)") (class "Default")
      (node (ref "IC6") (pin "6") (pinfunction "RA4/T0CKI/CIOUT/RCV_6") (pintype "bidirectional"))
      (node (ref "SV6") (pin "2") (pinfunction "2_2") (pintype "passive"))
    )
    (net (code "70") (name "Net-(IC6-RA5{slash}AN4{slash}~{SS}{slash}HLVDIN{slash}C2OUT)") (class "Default")
      (node (ref "IC6") (pin "7") (pinfunction "RA5/AN4/~{SS}/HLVDIN/C2OUT_7") (pintype "bidirectional"))
      (node (ref "SV6") (pin "1") (pinfunction "1_1") (pintype "passive"))
    )
    (net (code "71") (name "Net-(IC6-RA6{slash}OSC2{slash}CLKO)") (class "Default")
      (node (ref "C14") (pin "1") (pinfunction "1_1") (pintype "passive"))
      (node (ref "IC6") (pin "14") (pinfunction "RA6/OSC2/CLKO_14") (pintype "output"))
      (node (ref "Q1") (pin "2") (pinfunction "2_2") (pintype "passive"))
    )
    (net (code "72") (name "Net-(IC6-RC4{slash}D-{slash}VM)") (class "Default")
      (node (ref "IC6") (pin "23") (pinfunction "RC4/D-/VM_23") (pintype "bidirectional"))
      (node (ref "USB") (pin "2") (pinfunction "2_2") (pintype "passive"))
    )
    (net (code "73") (name "Net-(IC6-RC5{slash}D+{slash}VP)") (class "Default")
      (node (ref "IC6") (pin "24") (pinfunction "RC5/D+/VP_24") (pintype "bidirectional"))
      (node (ref "USB") (pin "3") (pinfunction "3_3") (pintype "passive"))
    )
    (net (code "74") (name "Net-(IC6-VUSB)") (class "Default")
      (node (ref "C15") (pin "+") (pinfunction "+_+") (pintype "passive"))
      (node (ref "IC6") (pin "18") (pinfunction "VUSB_18") (pintype "bidirectional"))
    )
    (net (code "75") (name "Net-(IC6-~{MCLR}{slash}VPP{slash}RE3)") (class "Default")
      (node (ref "IC6") (pin "1") (pinfunction "~{MCLR}/VPP/RE3_1") (pintype "input"))
      (node (ref "ISCP") (pin "1") (pinfunction "1_1") (pintype "passive"))
      (node (ref "R19") (pin "2") (pinfunction "2_2") (pintype "passive"))
      (node (ref "RESET1") (pin "2") (pinfunction "S1_2") (pintype "passive"))
    )
    (net (code "76") (name "Net-(LED1-PadA)") (class "Default")
      (node (ref "LED1") (pin "A") (pinfunction "A_A") (pintype "passive"))
      (node (ref "R21") (pin "2") (pinfunction "2_2") (pintype "passive"))
    )
    (net (code "77") (name "Net-(LED2-PadA)") (class "Default")
      (node (ref "LED2") (pin "A") (pinfunction "A_A") (pintype "passive"))
      (node (ref "R22") (pin "2") (pinfunction "2_2") (pintype "passive"))
    )
    (net (code "78") (name "Net-(R5-A)") (class "Default")
      (node (ref "R3") (pin "2") (pinfunction "2_2") (pintype "passive"))
      (node (ref "R5") (pin "3") (pinfunction "A_3") (pintype "passive"))
    )
    (net (code "79") (name "Net-(R12-A)") (class "Default")
      (node (ref "R10") (pin "2") (pinfunction "2_2") (pintype "passive"))
      (node (ref "R12") (pin "3") (pinfunction "A_3") (pintype "passive"))
    )
    (net (code "80") (name "Net-(R15-Pad1)") (class "Default")
      (node (ref "R15") (pin "1") (pinfunction "1_1") (pintype "passive"))
      (node (ref "R16") (pin "1") (pinfunction "1_1") (pintype "passive"))
      (node (ref "R21") (pin "1") (pinfunction "1_1") (pintype "passive"))
      (node (ref "USB") (pin "1") (pinfunction "1_1") (pintype "passive"))
    )
    (net (code "81") (name "Net-(R20-Pad1)") (class "Default")
      (node (ref "R20") (pin "1") (pinfunction "1_1") (pintype "passive"))
      (node (ref "T1") (pin "E") (pinfunction "E_E") (pintype "passive"))
    )
    (net (code "82") (name "Net-(R20-Pad2)") (class "Default")
      (node (ref "R20") (pin "2") (pinfunction "2_2") (pintype "passive"))
      (node (ref "R20") (pin "3") (pinfunction "3_3") (pintype "passive"))
      (node (ref "SV9") (pin "1") (pinfunction "1_1") (pintype "passive"))
    )
    (net (code "83") (name "Net-(R42-Pad3)") (class "Default")
      (node (ref "R42") (pin "3") (pinfunction "3_3") (pintype "passive"))
      (node (ref "SV9") (pin "5") (pinfunction "5_5") (pintype "passive"))
    )
    (net (code "84") (name "Net-(SV2-Pad1)") (class "Default")
      (node (ref "SV2") (pin "1") (pinfunction "1_1") (pintype "passive"))
      (node (ref "SV2") (pin "4") (pinfunction "4_4") (pintype "passive"))
      (node (ref "SV2") (pin "6") (pinfunction "6_6") (pintype "passive"))
    )
    (net (code "85") (name "R1") (class "Default")
      (node (ref "IC6") (pin "38") (pinfunction "RB5/KBI1/PGM_38") (pintype "bidirectional"))
      (node (ref "JP3") (pin "1") (pinfunction "1_1") (pintype "passive"))
    )
    (net (code "86") (name "R2") (class "Default")
      (node (ref "IC6") (pin "34") (pinfunction "RB1/AN10/INT1/SCK/SCL_34") (pintype "bidirectional"))
      (node (ref "JP4") (pin "1") (pinfunction "1_1") (pintype "passive"))
    )
    (net (code "87") (name "RS") (class "Default")
      (node (ref "IC6") (pin "21") (pinfunction "RD2/SPP2_21") (pintype "bidirectional"))
      (node (ref "SV10") (pin "1") (pinfunction "1_1") (pintype "passive"))
    )
    (net (code "88") (name "RTS") (class "Default")
      (node (ref "IC6") (pin "16") (pinfunction "RC1/T1OSI/ICCP2/~{UOE}_16") (pintype "bidirectional"))
      (node (ref "SV3") (pin "6") (pinfunction "6_6") (pintype "passive"))
    )
    (net (code "89") (name "RX") (class "Default")
      (node (ref "IC6") (pin "26") (pinfunction "RC7/RX/DT/SDO_26") (pintype "bidirectional"))
      (node (ref "SV3") (pin "2") (pinfunction "2_2") (pintype "passive"))
    )
    (net (code "90") (name "S1") (class "Default")
      (node (ref "IC1") (pin "14") (pinfunction "SENS1_14") (pintype "output"))
      (node (ref "IC2") (pin "1") (pinfunction "SEN_A_1") (pintype "input"))
      (node (ref "R2") (pin "2") (pinfunction "2_2") (pintype "passive"))
      (node (ref "R9") (pin "2") (pinfunction "2_2") (pintype "passive"))
    )
    (net (code "91") (name "S2") (class "Default")
      (node (ref "IC1") (pin "13") (pinfunction "SENS2_13") (pintype "output"))
      (node (ref "IC2") (pin "15") (pinfunction "SEN_B_15") (pintype "input"))
      (node (ref "R1") (pin "2") (pinfunction "2_2") (pintype "passive"))
      (node (ref "R8") (pin "2") (pinfunction "2_2") (pintype "passive"))
    )
    (net (code "92") (name "S3") (class "Default")
      (node (ref "IC3") (pin "14") (pinfunction "SENS1_14") (pintype "output"))
      (node (ref "IC4") (pin "1") (pinfunction "SEN_A_1") (pintype "input"))
      (node (ref "R14") (pin "2") (pinfunction "2_2") (pintype "passive"))
      (node (ref "R7") (pin "2") (pinfunction "2_2") (pintype "passive"))
    )
    (net (code "93") (name "S4") (class "Default")
      (node (ref "IC3") (pin "13") (pinfunction "SENS2_13") (pintype "output"))
      (node (ref "IC4") (pin "15") (pinfunction "SEN_B_15") (pintype "input"))
      (node (ref "R13") (pin "2") (pinfunction "2_2") (pintype "passive"))
      (node (ref "R6") (pin "2") (pinfunction "2_2") (pintype "passive"))
    )
    (net (code "94") (name "ST1") (class "Default")
      (node (ref "IC1") (pin "19") (pinfunction "H/F_19") (pintype "input"))
      (node (ref "IC6") (pin "9") (pinfunction "RE1/AN6/CK2SPP_9") (pintype "bidirectional"))
    )
    (net (code "95") (name "ST2") (class "Default")
      (node (ref "IC3") (pin "19") (pinfunction "H/F_19") (pintype "input"))
      (node (ref "IC6") (pin "10") (pinfunction "RE2/AN7/OESPP_10") (pintype "bidirectional"))
    )
    (net (code "96") (name "TX") (class "Default")
      (node (ref "IC6") (pin "25") (pinfunction "RC6/TX/CK_25") (pintype "bidirectional"))
      (node (ref "SV3") (pin "4") (pinfunction "4_4") (pintype "passive"))
    )
    (net (code "97") (name "USBD") (class "Default")
      (node (ref "IC6") (pin "15") (pinfunction "RC0/TIOSO/T13CKI_15") (pintype "bidirectional"))
      (node (ref "R15") (pin "2") (pinfunction "2_2") (pintype "passive"))
    )
    (net (code "98") (name "VDD") (class "Default")
      (node (ref "C11") (pin "1") (pinfunction "1_1") (pintype "passive"))
      (node (ref "C9") (pin "-") (pinfunction "-_-") (pintype "passive"))
      (node (ref "D18") (pin "A") (pinfunction "A_A") (pintype "passive"))
      (node (ref "IC1") (pin "12") (pinfunction "VCC_12") (pintype "power_in"))
      (node (ref "IC2") (pin "9") (pinfunction "VCC_9") (pintype "power_in"))
      (node (ref "IC3") (pin "12") (pinfunction "VCC_12") (pintype "power_in"))
      (node (ref "IC4") (pin "9") (pinfunction "VCC_9") (pintype "power_in"))
      (node (ref "IC5") (pin "16") (pinfunction "VCC_16") (pintype "power_in"))
      (node (ref "IC6") (pin "11") (pinfunction "VDD_11") (pintype "power_in"))
      (node (ref "IC6") (pin "32") (pinfunction "VDD_32") (pintype "power_in"))
      (node (ref "IC7") (pin "3") (pinfunction "VO_3") (pintype "passive"))
      (node (ref "ISCP") (pin "2") (pinfunction "2_2") (pintype "passive"))
      (node (ref "R10") (pin "1") (pinfunction "1_1") (pintype "passive"))
      (node (ref "R11") (pin "2") (pinfunction "2_2") (pintype "passive"))
      (node (ref "R17") (pin "1") (pinfunction "1_1") (pintype "passive"))
      (node (ref "R18") (pin "1") (pinfunction "1_1") (pintype "passive"))
      (node (ref "R22") (pin "1") (pinfunction "1_1") (pintype "passive"))
      (node (ref "R3") (pin "1") (pinfunction "1_1") (pintype "passive"))
      (node (ref "R4") (pin "2") (pinfunction "2_2") (pintype "passive"))
      (node (ref "R42") (pin "1") (pinfunction "1_1") (pintype "passive"))
      (node (ref "SV9") (pin "4") (pinfunction "4_4") (pintype "passive"))
      (node (ref "T1") (pin "C") (pinfunction "C_C") (pintype "passive"))
    )
    (net (code "99") (name "VDET") (class "Default")
      (node (ref "IC6") (pin "17") (pinfunction "RC2/CCP1/P1A_17") (pintype "bidirectional"))
      (node (ref "R17") (pin "2") (pinfunction "2_2") (pintype "passive"))
    )
    (net (code "100") (name "VS") (class "Default")
      (node (ref "C12") (pin "+") (pinfunction "+_+") (pintype "passive"))
      (node (ref "D10") (pin "C") (pinfunction "C_C") (pintype "passive"))
      (node (ref "D11") (pin "C") (pinfunction "C_C") (pintype "passive"))
      (node (ref "D12") (pin "C") (pinfunction "C_C") (pintype "passive"))
      (node (ref "D5") (pin "C") (pinfunction "C_C") (pintype "passive"))
      (node (ref "D6") (pin "C") (pinfunction "C_C") (pintype "passive"))
      (node (ref "D7") (pin "C") (pinfunction "C_C") (pintype "passive"))
      (node (ref "D8") (pin "C") (pinfunction "C_C") (pintype "passive"))
      (node (ref "D9") (pin "C") (pinfunction "C_C") (pintype "passive"))
      (node (ref "IC2") (pin "4") (pinfunction "VS_4") (pintype "power_in"))
      (node (ref "IC4") (pin "4") (pinfunction "VS_4") (pintype "power_in"))
      (node (ref "IC7") (pin "1") (pinfunction "VI_1") (pintype "input"))
      (node (ref "X5") (pin "1") (pinfunction "KL_1") (pintype "passive"))
    )
    (net (code "101") (name "unconnected-(IC6-RD0{slash}SPP0-Pad19)") (class "Default")
      (node (ref "IC6") (pin "19") (pinfunction "RD0/SPP0_19") (pintype "bidirectional"))
    )
    (net (code "102") (name "unconnected-(IC6-RD1{slash}SPP1-Pad20)") (class "Default")
      (node (ref "IC6") (pin "20") (pinfunction "RD1/SPP1_20") (pintype "bidirectional"))
    )
    (net (code "103") (name "unconnected-(ISCP-Pad6)") (class "Default")
      (node (ref "ISCP") (pin "6") (pinfunction "6_6") (pintype "passive"))
    )
    (net (code "104") (name "unconnected-(RESET1-P-Pad3)") (class "Default")
      (node (ref "RESET1") (pin "3") (pinfunction "P_3") (pintype "passive"))
    )
    (net (code "105") (name "unconnected-(RESET1-S-Pad1)") (class "Default")
      (node (ref "RESET1") (pin "1") (pinfunction "S_1") (pintype "passive"))
    )
    (net (code "106") (name "unconnected-(SV2-Pad9)") (class "Default")
      (node (ref "SV2") (pin "9") (pinfunction "9_9") (pintype "passive"))
    )
    (net (code "107") (name "unconnected-(SV2-Pad10)") (class "Default")
      (node (ref "SV2") (pin "10") (pinfunction "10_10") (pintype "passive"))
    )
  )
)
